# OSD19001_USB.net
KiCad netlist of a schematic drawn in Altium Designer
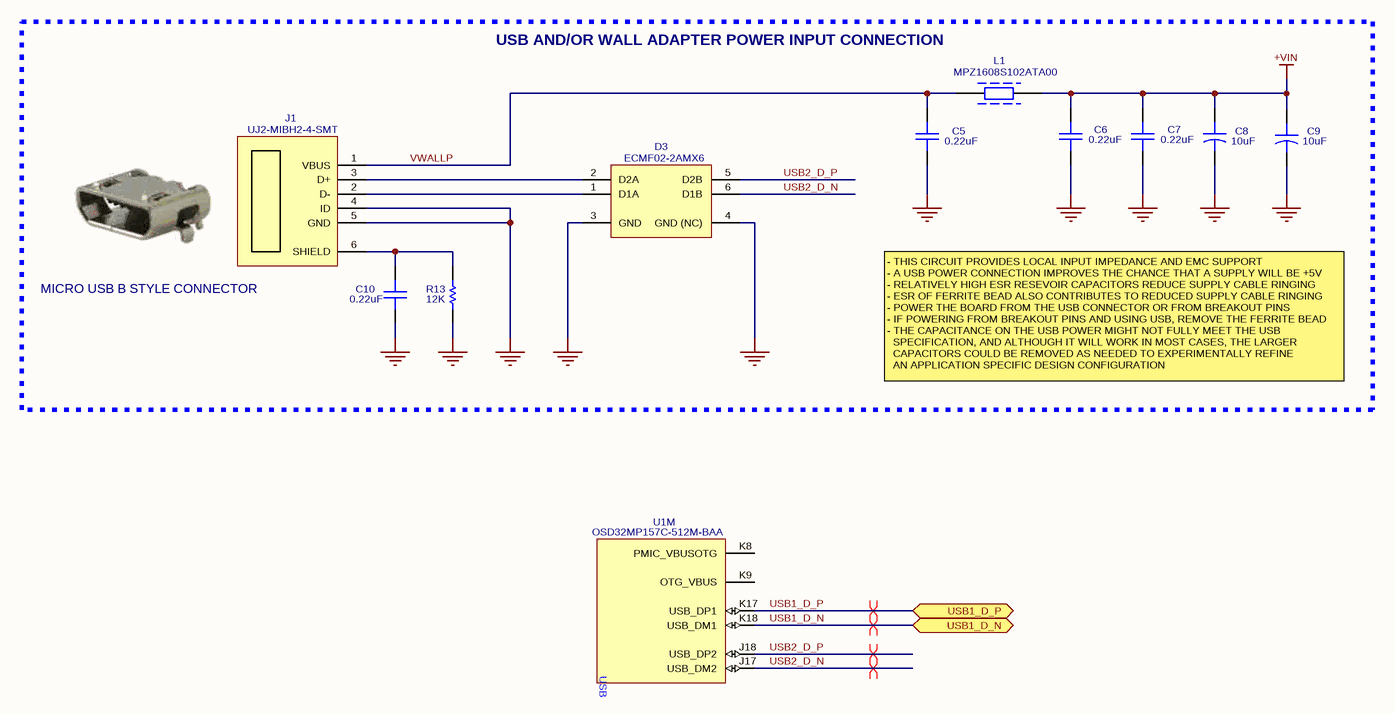
[diagram p0: OSD19001_USB.SchDoc]

(export (version "E")
  (design (tool "Eeschema 10.0.6"))
  (components
    (comp (ref "C5")
      (value "0.22uF")
      (footprint "LP_0603_HIGH")
      (fields (field (name "TOLERANCE") "10%") (field (name "VOLTAGE") "25V"))
      (libsource (lib "ACWPrimitives") (part "CERCAP"))
    )
    (comp (ref "C6")
      (value "0.22uF")
      (footprint "LP_0603_HIGH")
      (fields (field (name "TOLERANCE") "10%") (field (name "VOLTAGE") "25V"))
      (libsource (lib "ACWPrimitives") (part "CERCAP"))
    )
    (comp (ref "C7")
      (value "0.22uF")
      (footprint "LP_0603_HIGH")
      (fields (field (name "TOLERANCE") "10%") (field (name "VOLTAGE") "25V"))
      (libsource (lib "ACWPrimitives") (part "CERCAP"))
    )
    (comp (ref "C8")
      (value "10uF")
      (footprint "LP_EIAB")
      (fields (field (name "TOLERANCE") "20%") (field (name "VOLTAGE") "10V"))
      (libsource (lib "ACWPrimitives") (part "POLCAP"))
    )
    (comp (ref "C9")
      (value "10uF")
      (footprint "LP_EIAB")
      (fields (field (name "TOLERANCE") "20%") (field (name "VOLTAGE") "10V"))
      (libsource (lib "ACWPrimitives") (part "POLCAP"))
    )
    (comp (ref "C10")
      (value "0.22uF")
      (footprint "LP_0603_HIGH")
      (fields (field (name "TOLERANCE") "10%") (field (name "VOLTAGE") "25V"))
      (libsource (lib "ACWPrimitives") (part "CERCAP"))
    )
    (comp (ref "D3")
      (value "ECMF02-2AMX6")
      (footprint "DFN6_6L_ST")
      (description "USB Filter And ESD Protection")
      (libsource (lib "ACWSemiconductors") (part "ECMF02-2AMX6"))
    )
    (comp (ref "J1")
      (value "UJ2-MIBH2-4-SMT")
      (footprint "CUI_UJ2-MIBH2-4-SMT")
      (description "USB Micro B Connetor")
      (libsource (lib "ACWConnectors") (part "USB_MICRO_B"))
    )
    (comp (ref "L1")
      (value "MPZ1608S102ATA00")
      (footprint "LP_0603_IND")
      (libsource (lib "ACWPrimitives") (part "BEAD"))
    )
    (comp (ref "R13")
      (value "12K")
      (footprint "LP_0603_LOW")
      (fields (field (name "TOLERANCE") "5%") (field (name "POWER") "0.1W") (field (name "VOLTAGE") "50V"))
      (libsource (lib "ACWPrimitives") (part "RESISTOR"))
    )
    (comp (ref "U1")
      (value "OSD32MP157C-512M-BAA")
      (footprint "BGA_OCTAVO_SIP_OSD32MP157C")
      (description "Octavo ST Processor SIP")
      (fields (field (name "MANUFACTURER") "Octavo Systems"))
      (libsource (lib "ACWModules") (part "OSD32MP157C"))
    )
  )
  (nets
    (net (code "1") (name "+VIN") (class "Default")
      (node (ref "C6") (pin "2") (pinfunction "2_2") (pintype "passive"))
      (node (ref "C7") (pin "2") (pinfunction "2_2") (pintype "passive"))
      (node (ref "C8") (pin "1") (pinfunction "1_1") (pintype "passive"))
      (node (ref "C9") (pin "1") (pinfunction "1_1") (pintype "passive"))
      (node (ref "L1") (pin "2") (pinfunction "2_2") (pintype "passive"))
    )
    (net (code "2") (name "/USB1_D_N") (class "Default")
      (node (ref "U1") (pin "K18") (pinfunction "USB_DM1_K18") (pintype "bidirectional"))
    )
    (net (code "3") (name "/USB1_D_P") (class "Default")
      (node (ref "U1") (pin "K17") (pinfunction "USB_DP1_K17") (pintype "bidirectional"))
    )
    (net (code "4") (name "/USB2_D_N") (class "Default")
      (node (ref "D3") (pin "6") (pinfunction "D1B_6") (pintype "passive"))
      (node (ref "U1") (pin "J17") (pinfunction "USB_DM2_J17") (pintype "bidirectional"))
    )
    (net (code "5") (name "/USB2_D_P") (class "Default")
      (node (ref "D3") (pin "5") (pinfunction "D2B_5") (pintype "passive"))
      (node (ref "U1") (pin "J18") (pinfunction "USB_DP2_J18") (pintype "bidirectional"))
    )
    (net (code "6") (name "/VWALLP") (class "Default")
      (node (ref "C5") (pin "2") (pinfunction "2_2") (pintype "passive"))
      (node (ref "J1") (pin "1") (pinfunction "VBUS_1") (pintype "passive"))
      (node (ref "L1") (pin "1") (pinfunction "1_1") (pintype "passive"))
    )
    (net (code "7") (name "GND") (class "Default")
      (node (ref "C10") (pin "1") (pinfunction "1_1") (pintype "passive"))
      (node (ref "C5") (pin "1") (pinfunction "1_1") (pintype "passive"))
      (node (ref "C6") (pin "1") (pinfunction "1_1") (pintype "passive"))
      (node (ref "C7") (pin "1") (pinfunction "1_1") (pintype "passive"))
      (node (ref "C8") (pin "2") (pinfunction "2_2") (pintype "passive"))
      (node (ref "C9") (pin "2") (pinfunction "2_2") (pintype "passive"))
      (node (ref "D3") (pin "3") (pinfunction "GND_3") (pintype "passive"))
      (node (ref "D3") (pin "4") (pinfunction "GND_(NC)_4") (pintype "passive"))
      (node (ref "J1") (pin "4") (pinfunction "ID_4") (pintype "passive"))
      (node (ref "J1") (pin "5") (pinfunction "GND_5") (pintype "passive"))
      (node (ref "R13") (pin "1") (pinfunction "1_1") (pintype "passive"))
    )
    (net (code "8") (name "Net-(D3-D1A)") (class "Default")
      (node (ref "D3") (pin "1") (pinfunction "D1A_1") (pintype "passive"))
      (node (ref "J1") (pin "2") (pinfunction "D-_2") (pintype "passive"))
    )
    (net (code "9") (name "Net-(D3-D2A)") (class "Default")
      (node (ref "D3") (pin "2") (pinfunction "D2A_2") (pintype "passive"))
      (node (ref "J1") (pin "3") (pinfunction "D+_3") (pintype "passive"))
    )
    (net (code "10") (name "Net-(J1-SHIELD)") (class "Default")
      (node (ref "C10") (pin "2") (pinfunction "2_2") (pintype "passive"))
      (node (ref "J1") (pin "6") (pinfunction "SHIELD_6") (pintype "passive"))
      (node (ref "R13") (pin "2") (pinfunction "2_2") (pintype "passive"))
    )
    (net (code "11") (name "unconnected-(U1M-OTG_VBUS-PadK9)") (class "Default")
      (node (ref "U1") (pin "K9") (pinfunction "OTG_VBUS_K9") (pintype "passive"))
    )
    (net (code "12") (name "unconnected-(U1M-PMIC_VBUSOTG-PadK8)") (class "Default")
      (node (ref "U1") (pin "K8") (pinfunction "PMIC_VBUSOTG_K8") (pintype "passive"))
    )
  )
)
